# shield.net
KiCad netlist of a schematic drawn in EAGLE
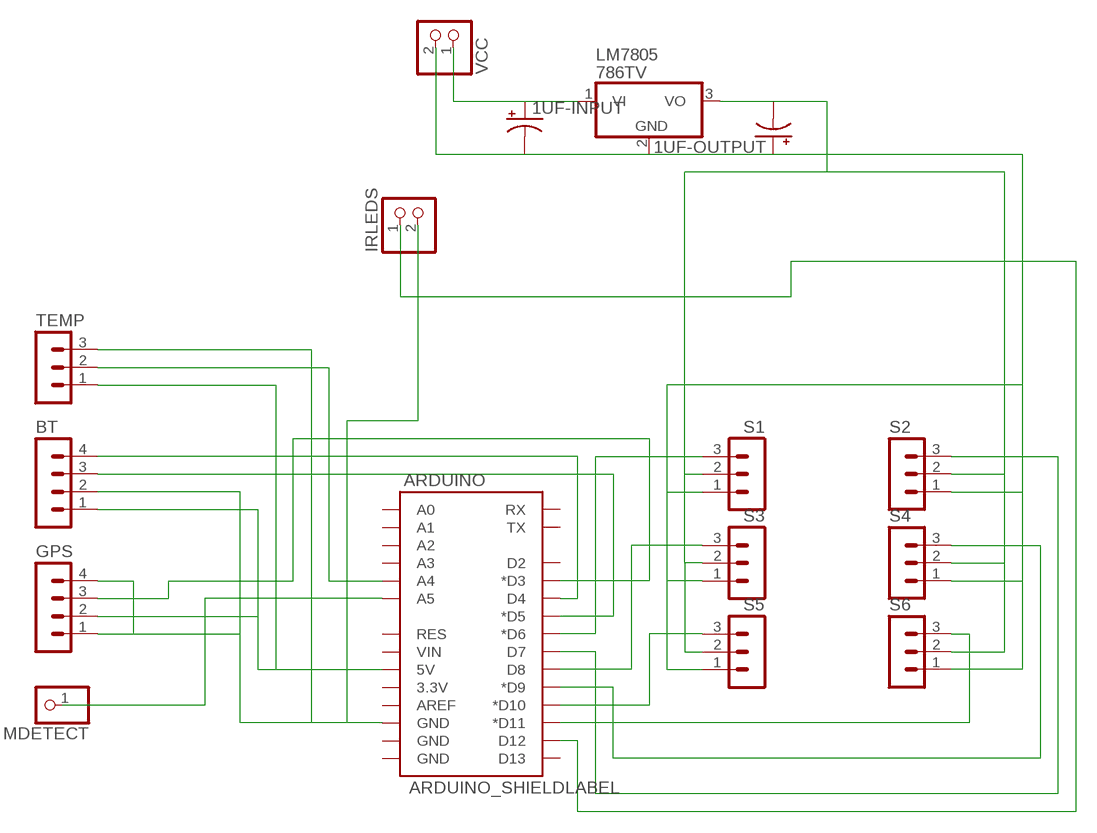
[diagram p0: schematic, sheet 1]

(export (version "E")
  (design (tool "Eeschema 10.0.6"))
  (components
    (comp (ref "1UF-INPUT")
      (value "CAP_POLPTH4")
      (footprint "eagle-import:CPOL-RADIAL-1000UF-25V")
      (libsource (lib "eagle-import") (part "CAP_POLPTH4"))
    )
    (comp (ref "1UF-OUTPUT")
      (value "CAP_POLPTH4")
      (footprint "eagle-import:CPOL-RADIAL-1000UF-25V")
      (libsource (lib "eagle-import") (part "CAP_POLPTH4"))
    )
    (comp (ref "ARDUINO")
      (value "ARDUINO_SHIELDLABEL")
      (footprint "eagle-import:DUEMILANOVE_SHIELD")
      (libsource (lib "eagle-import") (part "ARDUINO_SHIELDLABEL"))
    )
    (comp (ref "BT")
      (value "MA04-1")
      (footprint "eagle-import:MA04-1")
      (libsource (lib "eagle-import") (part "MA04-1"))
    )
    (comp (ref "GPS")
      (value "MA04-1")
      (footprint "eagle-import:MA04-1")
      (libsource (lib "eagle-import") (part "MA04-1"))
    )
    (comp (ref "IRLEDS")
      (value "PINHD-1X2")
      (footprint "eagle-import:1X02")
      (libsource (lib "eagle-import") (part "PINHD-1X2"))
    )
    (comp (ref "LM7805")
      (value "786TV")
      (footprint "eagle-import:TO220V")
      (libsource (lib "eagle-import") (part "78TV6"))
    )
    (comp (ref "MDETECT")
      (value "PINHD-1X1")
      (footprint "eagle-import:1X01")
      (libsource (lib "eagle-import") (part "PINHD-1X1"))
    )
    (comp (ref "S1")
      (value "MA03-1")
      (footprint "eagle-import:MA03-1")
      (libsource (lib "eagle-import") (part "MA03-1"))
    )
    (comp (ref "S2")
      (value "MA03-1")
      (footprint "eagle-import:MA03-1")
      (libsource (lib "eagle-import") (part "MA03-1"))
    )
    (comp (ref "S3")
      (value "MA03-1")
      (footprint "eagle-import:MA03-1")
      (libsource (lib "eagle-import") (part "MA03-1"))
    )
    (comp (ref "S4")
      (value "MA03-1")
      (footprint "eagle-import:MA03-1")
      (libsource (lib "eagle-import") (part "MA03-1"))
    )
    (comp (ref "S5")
      (value "MA03-1")
      (footprint "eagle-import:MA03-1")
      (libsource (lib "eagle-import") (part "MA03-1"))
    )
    (comp (ref "S6")
      (value "MA03-1")
      (footprint "eagle-import:MA03-1")
      (libsource (lib "eagle-import") (part "MA03-1"))
    )
    (comp (ref "TEMP")
      (value "MA03-1")
      (footprint "eagle-import:MA03-1")
      (libsource (lib "eagle-import") (part "MA03-1"))
    )
    (comp (ref "VCC")
      (value "PINHD-1X2")
      (footprint "eagle-import:1X02")
      (libsource (lib "eagle-import") (part "PINHD-1X2"))
    )
  )
  (nets
    (net (code "1") (name "Net-(1UF-INPUT-+)") (class "Default")
      (node (ref "1UF-INPUT") (pin "1") (pinfunction "+_1") (pintype "passive"))
      (node (ref "LM7805") (pin "1") (pinfunction "VI_1") (pintype "input"))
      (node (ref "VCC") (pin "1") (pinfunction "1_1") (pintype "passive"))
    )
    (net (code "2") (name "Net-(1UF-INPUT--)") (class "Default")
      (node (ref "1UF-INPUT") (pin "2") (pinfunction "-_2") (pintype "passive"))
      (node (ref "1UF-OUTPUT") (pin "1") (pinfunction "+_1") (pintype "passive"))
      (node (ref "LM7805") (pin "2") (pinfunction "GND_2") (pintype "passive"))
      (node (ref "S1") (pin "1") (pinfunction "1_1") (pintype "passive"))
      (node (ref "S2") (pin "1") (pinfunction "1_1") (pintype "passive"))
      (node (ref "S3") (pin "1") (pinfunction "1_1") (pintype "passive"))
      (node (ref "S4") (pin "1") (pinfunction "1_1") (pintype "passive"))
      (node (ref "S5") (pin "1") (pinfunction "1_1") (pintype "passive"))
      (node (ref "S6") (pin "1") (pinfunction "1_1") (pintype "passive"))
      (node (ref "VCC") (pin "2") (pinfunction "2_2") (pintype "passive"))
    )
    (net (code "3") (name "Net-(1UF-OUTPUT--)") (class "Default")
      (node (ref "1UF-OUTPUT") (pin "2") (pinfunction "-_2") (pintype "passive"))
      (node (ref "LM7805") (pin "3") (pinfunction "VO_3") (pintype "passive"))
      (node (ref "S1") (pin "2") (pinfunction "2_2") (pintype "passive"))
      (node (ref "S2") (pin "2") (pinfunction "2_2") (pintype "passive"))
      (node (ref "S3") (pin "2") (pinfunction "2_2") (pintype "passive"))
      (node (ref "S4") (pin "2") (pinfunction "2_2") (pintype "passive"))
      (node (ref "S5") (pin "2") (pinfunction "2_2") (pintype "passive"))
      (node (ref "S6") (pin "2") (pinfunction "2_2") (pintype "passive"))
    )
    (net (code "4") (name "Net-(ARDUINO-*D3)") (class "Default")
      (node (ref "ARDUINO") (pin "D3") (pinfunction "*D3_D3") (pintype "bidirectional"))
      (node (ref "GPS") (pin "3") (pinfunction "3_3") (pintype "passive"))
    )
    (net (code "5") (name "Net-(ARDUINO-*D5)") (class "Default")
      (node (ref "ARDUINO") (pin "D5") (pinfunction "*D5_D5") (pintype "bidirectional"))
      (node (ref "BT") (pin "3") (pinfunction "3_3") (pintype "passive"))
    )
    (net (code "6") (name "Net-(ARDUINO-*D6)") (class "Default")
      (node (ref "ARDUINO") (pin "D6") (pinfunction "*D6_D6") (pintype "bidirectional"))
      (node (ref "S1") (pin "3") (pinfunction "3_3") (pintype "passive"))
    )
    (net (code "7") (name "Net-(ARDUINO-*D9)") (class "Default")
      (node (ref "ARDUINO") (pin "D9") (pinfunction "*D9_D9") (pintype "bidirectional"))
      (node (ref "S4") (pin "3") (pinfunction "3_3") (pintype "passive"))
    )
    (net (code "8") (name "Net-(ARDUINO-*D10)") (class "Default")
      (node (ref "ARDUINO") (pin "D10") (pinfunction "*D10_D10") (pintype "bidirectional"))
      (node (ref "S5") (pin "3") (pinfunction "3_3") (pintype "passive"))
    )
    (net (code "9") (name "Net-(ARDUINO-*D11)") (class "Default")
      (node (ref "ARDUINO") (pin "D11") (pinfunction "*D11_D11") (pintype "bidirectional"))
      (node (ref "S6") (pin "3") (pinfunction "3_3") (pintype "passive"))
    )
    (net (code "10") (name "Net-(ARDUINO-GND-PadGND@2)") (class "Default")
      (node (ref "ARDUINO") (pin "GND@2") (pinfunction "GND_GND@2") (pintype "bidirectional"))
      (node (ref "BT") (pin "2") (pinfunction "2_2") (pintype "passive"))
      (node (ref "GPS") (pin "1") (pinfunction "1_1") (pintype "passive"))
      (node (ref "GPS") (pin "4") (pinfunction "4_4") (pintype "passive"))
      (node (ref "IRLEDS") (pin "2") (pinfunction "2_2") (pintype "passive"))
      (node (ref "TEMP") (pin "3") (pinfunction "3_3") (pintype "passive"))
    )
    (net (code "11") (name "Net-(ARDUINO-Pad5V)") (class "Default")
      (node (ref "ARDUINO") (pin "5V") (pinfunction "5V_5V") (pintype "bidirectional"))
      (node (ref "BT") (pin "1") (pinfunction "1_1") (pintype "passive"))
      (node (ref "GPS") (pin "2") (pinfunction "2_2") (pintype "passive"))
      (node (ref "TEMP") (pin "1") (pinfunction "1_1") (pintype "passive"))
    )
    (net (code "12") (name "Net-(ARDUINO-PadA4)") (class "Default")
      (node (ref "ARDUINO") (pin "A4") (pinfunction "A4_A4") (pintype "bidirectional"))
      (node (ref "TEMP") (pin "2") (pinfunction "2_2") (pintype "passive"))
    )
    (net (code "13") (name "Net-(ARDUINO-PadA5)") (class "Default")
      (node (ref "ARDUINO") (pin "A5") (pinfunction "A5_A5") (pintype "bidirectional"))
      (node (ref "MDETECT") (pin "1") (pinfunction "1_1") (pintype "passive"))
    )
    (net (code "14") (name "Net-(ARDUINO-PadD4)") (class "Default")
      (node (ref "ARDUINO") (pin "D4") (pinfunction "D4_D4") (pintype "bidirectional"))
      (node (ref "BT") (pin "4") (pinfunction "4_4") (pintype "passive"))
    )
    (net (code "15") (name "Net-(ARDUINO-PadD7)") (class "Default")
      (node (ref "ARDUINO") (pin "D7") (pinfunction "D7_D7") (pintype "bidirectional"))
      (node (ref "S2") (pin "3") (pinfunction "3_3") (pintype "passive"))
    )
    (net (code "16") (name "Net-(ARDUINO-PadD8)") (class "Default")
      (node (ref "ARDUINO") (pin "D8") (pinfunction "D8_D8") (pintype "bidirectional"))
      (node (ref "S3") (pin "3") (pinfunction "3_3") (pintype "passive"))
    )
    (net (code "17") (name "Net-(ARDUINO-PadD12)") (class "Default")
      (node (ref "ARDUINO") (pin "D12") (pinfunction "D12_D12") (pintype "bidirectional"))
      (node (ref "IRLEDS") (pin "1") (pinfunction "1_1") (pintype "passive"))
    )
    (net (code "18") (name "unconnected-(ARDUINO-GND-PadGND@0)") (class "Default")
      (node (ref "ARDUINO") (pin "GND@0") (pinfunction "GND_GND@0") (pintype "bidirectional"))
    )
    (net (code "19") (name "unconnected-(ARDUINO-GND-PadGND@1)") (class "Default")
      (node (ref "ARDUINO") (pin "GND@1") (pinfunction "GND_GND@1") (pintype "bidirectional"))
    )
    (net (code "20") (name "unconnected-(ARDUINO-Pad3.3V)") (class "Default")
      (node (ref "ARDUINO") (pin "3.3V") (pinfunction "3.3V_3.3V") (pintype "bidirectional"))
    )
    (net (code "21") (name "unconnected-(ARDUINO-PadA0)") (class "Default")
      (node (ref "ARDUINO") (pin "A0") (pinfunction "A0_A0") (pintype "bidirectional"))
    )
    (net (code "22") (name "unconnected-(ARDUINO-PadA1)") (class "Default")
      (node (ref "ARDUINO") (pin "A1") (pinfunction "A1_A1") (pintype "bidirectional"))
    )
    (net (code "23") (name "unconnected-(ARDUINO-PadA2)") (class "Default")
      (node (ref "ARDUINO") (pin "A2") (pinfunction "A2_A2") (pintype "bidirectional"))
    )
    (net (code "24") (name "unconnected-(ARDUINO-PadA3)") (class "Default")
      (node (ref "ARDUINO") (pin "A3") (pinfunction "A3_A3") (pintype "bidirectional"))
    )
    (net (code "25") (name "unconnected-(ARDUINO-PadAREF)") (class "Default")
      (node (ref "ARDUINO") (pin "AREF") (pinfunction "AREF_AREF") (pintype "bidirectional"))
    )
    (net (code "26") (name "unconnected-(ARDUINO-PadD2)") (class "Default")
      (node (ref "ARDUINO") (pin "D2") (pinfunction "D2_D2") (pintype "bidirectional"))
    )
    (net (code "27") (name "unconnected-(ARDUINO-PadD13)") (class "Default")
      (node (ref "ARDUINO") (pin "D13") (pinfunction "D13_D13") (pintype "bidirectional"))
    )
    (net (code "28") (name "unconnected-(ARDUINO-PadRES)") (class "Default")
      (node (ref "ARDUINO") (pin "RES") (pinfunction "RES_RES") (pintype "bidirectional"))
    )
    (net (code "29") (name "unconnected-(ARDUINO-PadRX)") (class "Default")
      (node (ref "ARDUINO") (pin "RX") (pinfunction "RX_RX") (pintype "bidirectional"))
    )
    (net (code "30") (name "unconnected-(ARDUINO-PadTX)") (class "Default")
      (node (ref "ARDUINO") (pin "TX") (pinfunction "TX_TX") (pintype "bidirectional"))
    )
    (net (code "31") (name "unconnected-(ARDUINO-PadVIN)") (class "Default")
      (node (ref "ARDUINO") (pin "VIN") (pinfunction "VIN_VIN") (pintype "bidirectional"))
    )
  )
)
